# Four-Buttons.net
KiCad netlist of a schematic drawn in EAGLE
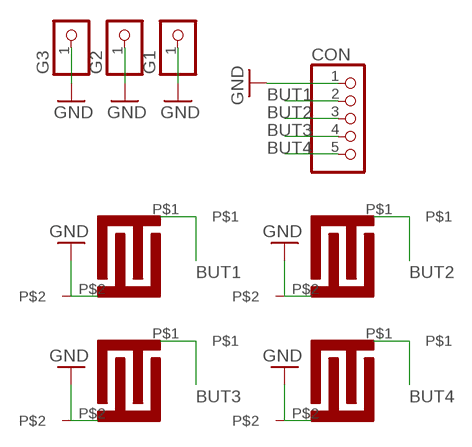
[diagram p0: schematic, sheet 1]

(export (version "E")
  (design (tool "Eeschema 10.0.6"))
  (components
    (comp (ref "BTN1")
      (value "BTN_1")
      (footprint "eagle-import:BTN_1")
      (libsource (lib "eagle-import") (part "BTN_1"))
    )
    (comp (ref "BTN2")
      (value "BTN_1")
      (footprint "eagle-import:BTN_1")
      (libsource (lib "eagle-import") (part "BTN_1"))
    )
    (comp (ref "BTN3")
      (value "BTN_1")
      (footprint "eagle-import:BTN_1")
      (libsource (lib "eagle-import") (part "BTN_1"))
    )
    (comp (ref "BTN4")
      (value "BTN_1")
      (footprint "eagle-import:BTN_1")
      (libsource (lib "eagle-import") (part "BTN_1"))
    )
    (comp (ref "CON")
      (value "PINHD-1X5")
      (footprint "eagle-import:1X05")
      (libsource (lib "eagle-import") (part "PINHD-1X5"))
    )
    (comp (ref "G1")
      (value "PINHD-1X1")
      (footprint "eagle-import:1X01")
      (libsource (lib "eagle-import") (part "PINHD-1X1"))
    )
    (comp (ref "G2")
      (value "PINHD-1X1")
      (footprint "eagle-import:1X01")
      (libsource (lib "eagle-import") (part "PINHD-1X1"))
    )
    (comp (ref "G3")
      (value "PINHD-1X1")
      (footprint "eagle-import:1X01")
      (libsource (lib "eagle-import") (part "PINHD-1X1"))
    )
  )
  (nets
    (net (code "1") (name "/BUT1") (class "Default")
      (node (ref "BTN1") (pin "P$1") (pinfunction "P$1_P$1") (pintype "bidirectional"))
      (node (ref "CON") (pin "2") (pinfunction "2_2") (pintype "passive"))
    )
    (net (code "2") (name "/BUT2") (class "Default")
      (node (ref "BTN2") (pin "P$1") (pinfunction "P$1_P$1") (pintype "bidirectional"))
      (node (ref "CON") (pin "3") (pinfunction "3_3") (pintype "passive"))
    )
    (net (code "3") (name "/BUT3") (class "Default")
      (node (ref "BTN3") (pin "P$1") (pinfunction "P$1_P$1") (pintype "bidirectional"))
      (node (ref "CON") (pin "4") (pinfunction "4_4") (pintype "passive"))
    )
    (net (code "4") (name "/BUT4") (class "Default")
      (node (ref "BTN4") (pin "P$1") (pinfunction "P$1_P$1") (pintype "bidirectional"))
      (node (ref "CON") (pin "5") (pinfunction "5_5") (pintype "passive"))
    )
    (net (code "5") (name "GND") (class "Default")
      (node (ref "BTN1") (pin "P$2") (pinfunction "P$2_P$2") (pintype "bidirectional"))
      (node (ref "BTN2") (pin "P$2") (pinfunction "P$2_P$2") (pintype "bidirectional"))
      (node (ref "BTN3") (pin "P$2") (pinfunction "P$2_P$2") (pintype "bidirectional"))
      (node (ref "BTN4") (pin "P$2") (pinfunction "P$2_P$2") (pintype "bidirectional"))
      (node (ref "CON") (pin "1") (pinfunction "1_1") (pintype "passive"))
      (node (ref "G1") (pin "1") (pinfunction "1_1") (pintype "passive"))
      (node (ref "G2") (pin "1") (pinfunction "1_1") (pintype "passive"))
      (node (ref "G3") (pin "1") (pinfunction "1_1") (pintype "passive"))
    )
  )
)
